# Controller_power.net
KiCad netlist of a schematic drawn in Altium Designer
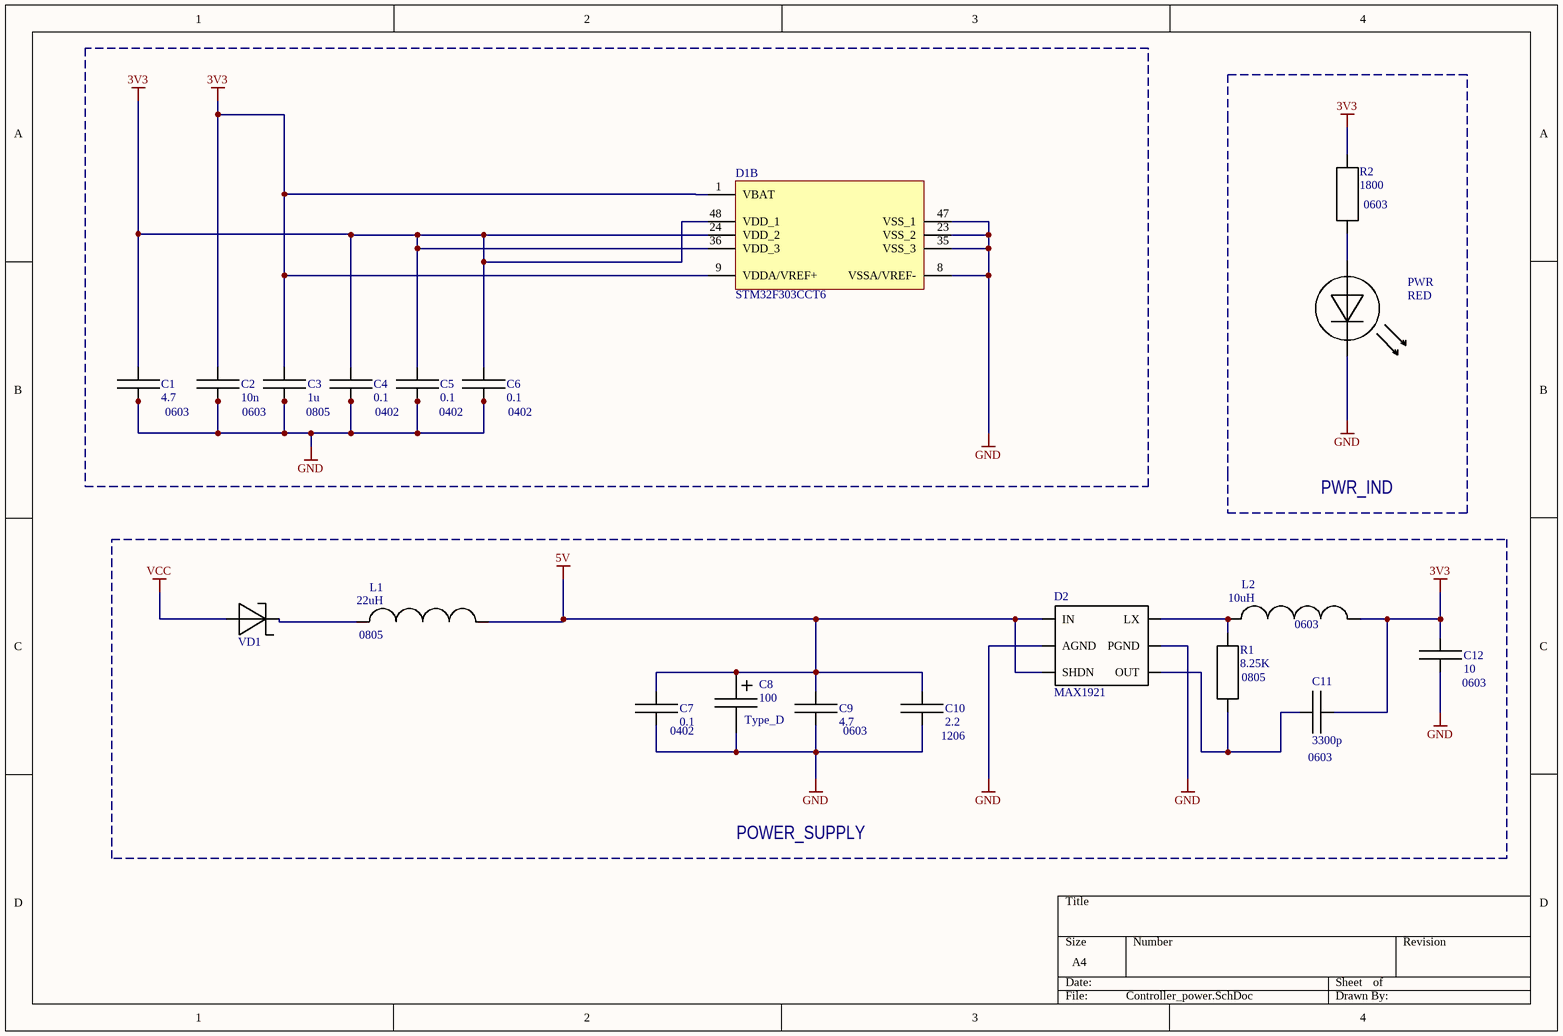
[diagram p0: Controller_power.SchDoc]

(export (version "E")
  (design (tool "Eeschema 10.0.6"))
  (components
    (comp (ref "C1")
      (value "4.7")
      (footprint "Mylibrary:SMD_0603_C")
      (libsource (lib "Mylibrary") (part "Capacitor"))
    )
    (comp (ref "C2")
      (value "10n")
      (footprint "Mylibrary:SMD_0603_C")
      (libsource (lib "Mylibrary") (part "Capacitor"))
    )
    (comp (ref "C3") (value "1u") (footprint "SMD_0805") (libsource (lib "Mylibrary") (part "Capacitor")))
    (comp (ref "C4")
      (value "0.1")
      (footprint "Mylibrary:SMD_0402_C")
      (libsource (lib "Mylibrary") (part "Capacitor"))
    )
    (comp (ref "C5")
      (value "0.1")
      (footprint "Mylibrary:SMD_0402_C")
      (libsource (lib "Mylibrary") (part "Capacitor"))
    )
    (comp (ref "C6")
      (value "0.1")
      (footprint "Mylibrary:SMD_0402_C")
      (libsource (lib "Mylibrary") (part "Capacitor"))
    )
    (comp (ref "C7")
      (value "0.1")
      (footprint "Mylibrary:SMD_0402_C")
      (libsource (lib "Mylibrary") (part "Capacitor"))
    )
    (comp (ref "C8")
      (value "100")
      (footprint "Mylibrary:SMD_7343")
      (libsource (lib "Mylibrary") (part "Capacitor polar"))
    )
    (comp (ref "C9")
      (value "4.7")
      (footprint "Mylibrary:SMD_0603_C")
      (libsource (lib "Mylibrary") (part "Capacitor"))
    )
    (comp (ref "C10") (value "2.2") (footprint "SMD_1206") (libsource (lib "Mylibrary") (part "Capacitor")))
    (comp (ref "C11")
      (value "3300p")
      (footprint "Mylibrary:SMD_0603_C")
      (libsource (lib "Mylibrary") (part "Capacitor"))
    )
    (comp (ref "C12")
      (value "10")
      (footprint "Mylibrary:SMD_0603_C")
      (libsource (lib "Mylibrary") (part "Capacitor"))
    )
    (comp (ref "D1")
      (value "STM32F303CCT6")
      (footprint "STM-LQFP48_N")
      (libsource (lib "STMicroelectronics STM32 F3") (part "STM32F303CCT6"))
    )
    (comp (ref "D2")
      (value "MAX1921")
      (footprint "Mylibrary:SOT23(95P280X145-6N)")
      (libsource (lib "Mylibrary") (part "MAX1921"))
    )
    (comp (ref "L1")
      (value "22uH")
      (footprint "Mylibrary:SMD_0805")
      (libsource (lib "Mylibrary") (part "Inductor"))
    )
    (comp (ref "L2")
      (value "10uH")
      (footprint "Mylibrary:SMD_0603")
      (libsource (lib "Mylibrary") (part "Inductor"))
    )
    (comp (ref "PWR")
      (value "RED")
      (footprint "Mylibrary:SMD_LED")
      (libsource (lib "Mylibrary") (part "LED_Diode"))
    )
    (comp (ref "R1")
      (value "8.25K")
      (footprint "Mylibrary:SMD_0805")
      (libsource (lib "Mylibrary") (part "Resistor"))
    )
    (comp (ref "R2")
      (value "1800")
      (footprint "SMD_0603")
      (description "0603 resistor")
      (libsource (lib "Mylibrary") (part "Resistor"))
    )
    (comp (ref "VD1")
      (value "Diode_schottky")
      (footprint "Mylibrary:SOD_123")
      (libsource (lib "Mylibrary") (part "Diode_schottky"))
    )
  )
  (nets
    (net (code "1") (name "3V3") (class "Default")
      (node (ref "C1") (pin "2") (pinfunction "2_2") (pintype "passive"))
      (node (ref "C11") (pin "2") (pinfunction "2_2") (pintype "passive"))
      (node (ref "C12") (pin "2") (pinfunction "2_2") (pintype "passive"))
      (node (ref "C2") (pin "2") (pinfunction "2_2") (pintype "passive"))
      (node (ref "C3") (pin "2") (pinfunction "2_2") (pintype "passive"))
      (node (ref "C4") (pin "2") (pinfunction "2_2") (pintype "passive"))
      (node (ref "C5") (pin "2") (pinfunction "2_2") (pintype "passive"))
      (node (ref "C6") (pin "2") (pinfunction "2_2") (pintype "passive"))
      (node (ref "D1") (pin "1") (pinfunction "VBAT_1") (pintype "power_in"))
      (node (ref "D1") (pin "24") (pinfunction "VDD_2_24") (pintype "power_in"))
      (node (ref "D1") (pin "36") (pinfunction "VDD_3_36") (pintype "power_in"))
      (node (ref "D1") (pin "48") (pinfunction "VDD_1_48") (pintype "power_in"))
      (node (ref "D1") (pin "9") (pinfunction "VDDA/VREF+_9") (pintype "power_in"))
      (node (ref "L2") (pin "2") (pinfunction "2_2") (pintype "passive"))
      (node (ref "R2") (pin "2") (pinfunction "2_2") (pintype "passive"))
    )
    (net (code "2") (name "5V") (class "Default")
      (node (ref "C10") (pin "2") (pinfunction "2_2") (pintype "passive"))
      (node (ref "C7") (pin "2") (pinfunction "2_2") (pintype "passive"))
      (node (ref "C8") (pin "1") (pinfunction "1_1") (pintype "passive"))
      (node (ref "C9") (pin "2") (pinfunction "2_2") (pintype "passive"))
      (node (ref "D2") (pin "1") (pinfunction "IN_1") (pintype "passive"))
      (node (ref "D2") (pin "3") (pinfunction "SHDN_3") (pintype "passive"))
      (node (ref "L1") (pin "2") (pinfunction "2_2") (pintype "passive"))
    )
    (net (code "3") (name "GND") (class "Default")
      (node (ref "C1") (pin "1") (pinfunction "1_1") (pintype "passive"))
      (node (ref "C10") (pin "1") (pinfunction "1_1") (pintype "passive"))
      (node (ref "C12") (pin "1") (pinfunction "1_1") (pintype "passive"))
      (node (ref "C2") (pin "1") (pinfunction "1_1") (pintype "passive"))
      (node (ref "C3") (pin "1") (pinfunction "1_1") (pintype "passive"))
      (node (ref "C4") (pin "1") (pinfunction "1_1") (pintype "passive"))
      (node (ref "C5") (pin "1") (pinfunction "1_1") (pintype "passive"))
      (node (ref "C6") (pin "1") (pinfunction "1_1") (pintype "passive"))
      (node (ref "C7") (pin "1") (pinfunction "1_1") (pintype "passive"))
      (node (ref "C8") (pin "2") (pinfunction "2_2") (pintype "passive"))
      (node (ref "C9") (pin "1") (pinfunction "1_1") (pintype "passive"))
      (node (ref "D1") (pin "23") (pinfunction "VSS_2_23") (pintype "power_in"))
      (node (ref "D1") (pin "35") (pinfunction "VSS_3_35") (pintype "power_in"))
      (node (ref "D1") (pin "47") (pinfunction "VSS_1_47") (pintype "power_in"))
      (node (ref "D1") (pin "8") (pinfunction "VSSA/VREF-_8") (pintype "power_in"))
      (node (ref "D2") (pin "2") (pinfunction "AGND_2") (pintype "passive"))
      (node (ref "D2") (pin "5") (pinfunction "PGND_5") (pintype "passive"))
      (node (ref "PWR") (pin "1") (pintype "passive"))
    )
    (net (code "4") (name "Net-(D2-LX)") (class "Default")
      (node (ref "D2") (pin "6") (pinfunction "LX_6") (pintype "passive"))
      (node (ref "L2") (pin "1") (pinfunction "1_1") (pintype "passive"))
      (node (ref "R1") (pin "2") (pinfunction "2_2") (pintype "passive"))
    )
    (net (code "5") (name "Net-(D2-OUT)") (class "Default")
      (node (ref "C11") (pin "1") (pinfunction "1_1") (pintype "passive"))
      (node (ref "D2") (pin "4") (pinfunction "OUT_4") (pintype "passive"))
      (node (ref "R1") (pin "1") (pinfunction "1_1") (pintype "passive"))
    )
    (net (code "6") (name "Net-(L1-Pad1)") (class "Default")
      (node (ref "L1") (pin "1") (pinfunction "1_1") (pintype "passive"))
      (node (ref "VD1") (pin "2") (pinfunction "2_2") (pintype "passive"))
    )
    (net (code "7") (name "Net-(PWR-Pad2)") (class "Default")
      (node (ref "PWR") (pin "2") (pintype "passive"))
      (node (ref "R2") (pin "1") (pinfunction "1_1") (pintype "passive"))
    )
    (net (code "8") (name "VCC") (class "Default")
      (node (ref "VD1") (pin "1") (pinfunction "1_1") (pintype "passive"))
    )
  )
)
